# main.net
KiCad netlist of a schematic drawn in Altium Designer
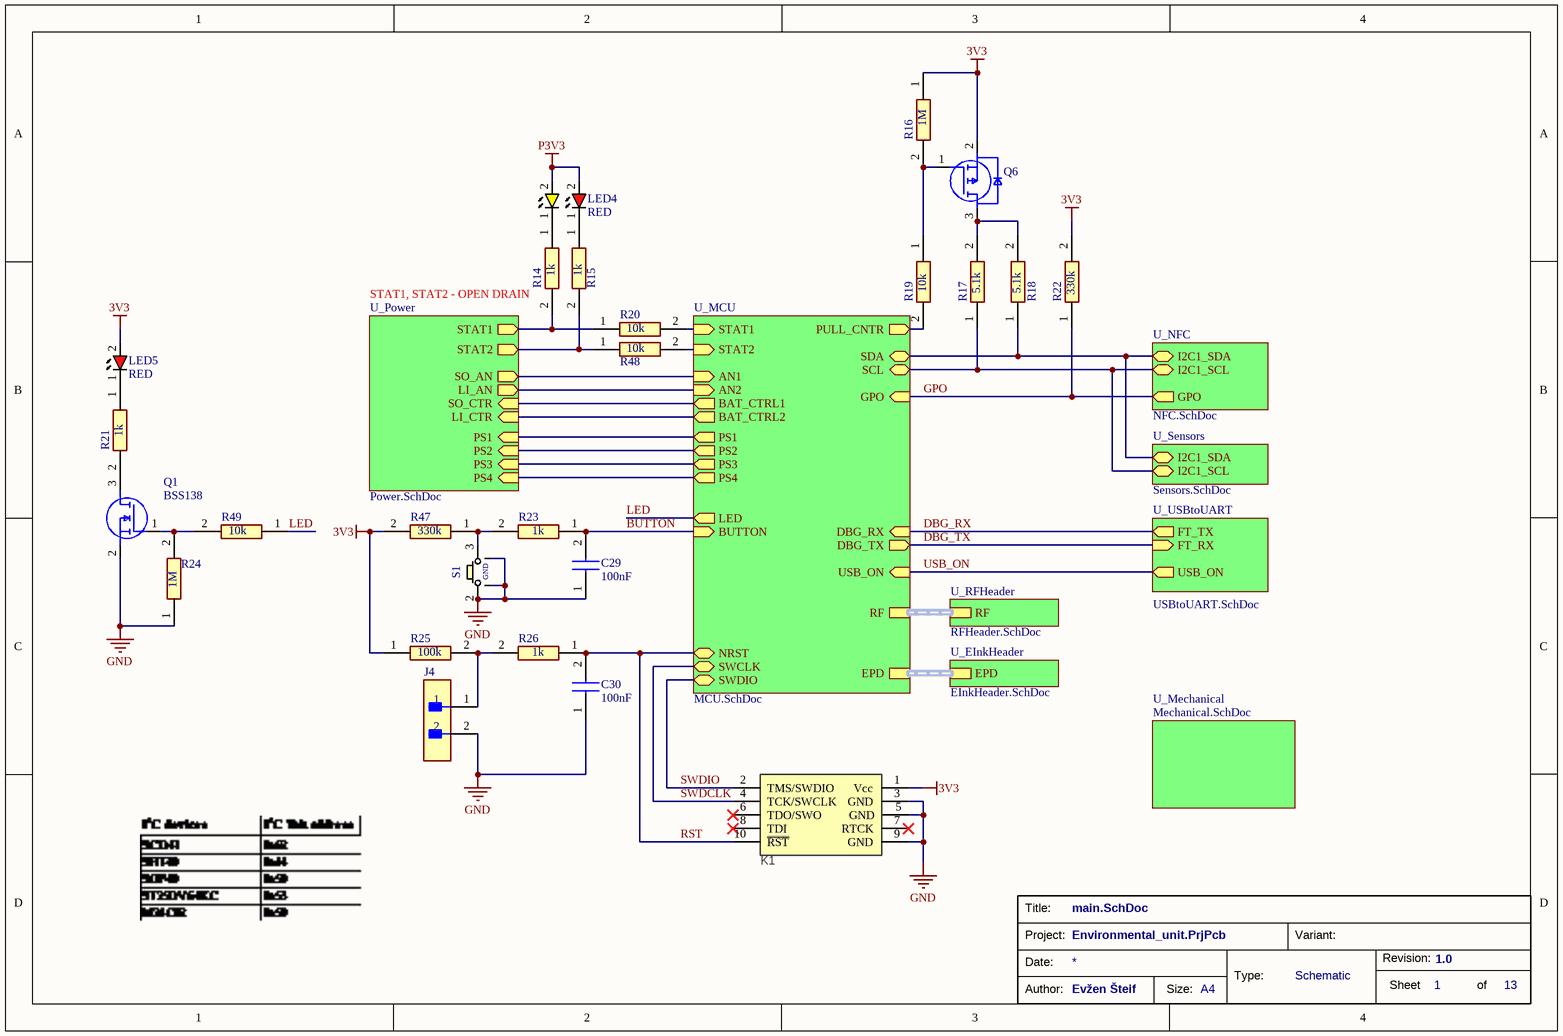
[diagram p0: main.SchDoc]

(export (version "E")
  (design (tool "Eeschema 10.0.6"))
  (components
    (comp (ref "C29")
      (value "100nF")
      (footprint "SamacSys:CAPC1005X70N")
      (description "Capacitor")
      (fields
        (field (name "MANUFACTURER_PART_NUMBER") "GRM155R61A104KA01D")
        (field (name "MOUSER PART NUMBER") "81-GRM155R61A104KA01")
      )
      (libsource (lib "*") (part "GRM155R61A104KA01D"))
    )
    (comp (ref "C30")
      (value "100nF")
      (footprint "SamacSys:CAPC1005X70N")
      (description "Capacitor")
      (fields
        (field (name "MANUFACTURER_PART_NUMBER") "GRM155R61A104KA01D")
        (field (name "MOUSER PART NUMBER") "81-GRM155R61A104KA01")
      )
      (libsource (lib "*") (part "GRM155R61A104KA01D"))
    )
    (comp (ref "J4")
      (value "M20-9990246")
      (footprint "FP-M20-9990246-MFG")
      (description "CONN HEADER VERT 2POS 2.54MM")
      (fields
        (field (name "OCTOPART") "https://octopart.com/m20-9990246-harwin-2590635")
        (field (name "MANUFACTURER") "Harwin")
      )
      (libsource (lib "Altium Content Vault") (part "3bc925449376181038e59eaffc5286c"))
    )
    (comp (ref "K1")
      (value "3220-10-0100-00")
      (footprint "IntLibGenerator:TH_CON_MHDR2X5_PIT50_KEY")
      (description "Cortex ARM JTAG 10 Pin, Header")
      (fields
        (field (name "PARTNUMBER") "TEST_00015")
        (field (name "MANUFACTURER") "CNC Tech")
        (field (name "AUTOR") "Krutina")
        (field (name "DESIGNER") "Krahulec")
        (field (name "LIBRARIAN") "Krahulec")
      )
      (libsource (lib "SamacSys") (part "TEST_00015"))
    )
    (comp (ref "LED3")
      (value "150060YS75000")
      (footprint "SamacSys:LEDC1608X80N")
      (description "LED")
      (fields (field (name "MOUSER PART NUMBER") "710-150060YS75000"))
      (libsource (lib "SamacSys") (part "150060YS75000"))
    )
    (comp (ref "LED4")
      (value "RED")
      (footprint "SamacSys:LEDC1608X80N")
      (description "LED")
      (fields
        (field (name "MANUFACTURER_PART_NUMBER") "150060RS75000")
        (field (name "MOUSER PART NUMBER") "710-150060RS75000")
      )
      (libsource (lib "SamacSys") (part "150060RS55040"))
    )
    (comp (ref "LED5")
      (value "RED")
      (footprint "SamacSys:LEDC1608X80N")
      (description "LED")
      (fields
        (field (name "MANUFACTURER_PART_NUMBER") "150060RS75000")
        (field (name "MOUSER PART NUMBER") "710-150060RS75000")
      )
      (libsource (lib "SamacSys") (part "150060RS55040"))
    )
    (comp (ref "Q1")
      (value "BSS138")
      (footprint "SamacSys:SOT95P240X120-3N")
      (description "MOSFET (N-Channel)")
      (fields (field (name "MOUSER PART NUMBER") "512-BSS138"))
      (libsource (lib "*") (part "BSS138"))
    )
    (comp (ref "Q6")
      (value "SSM3J358R,LF")
      (footprint "SamacSys:SOTFL95P240X88-3N")
      (description "MOSFET (P-Channel)")
      (fields (field (name "MOUSER PART NUMBER") "757-SSM3J358RLF"))
      (libsource (lib "SamacSys") (part "SSM3J358R,LF"))
    )
    (comp (ref "R14")
      (value "1k")
      (footprint "SamacSys:RESC1005X35N")
      (description "Resistor")
      (fields
        (field (name "MANUFACTURER_PART_NUMBER") "RT0402FRE071KL")
        (field (name "ARROW PART NUMBER") "RT0402FRE07100KL")
      )
      (libsource (lib "") (part "RT0402FRE071KL_1"))
    )
    (comp (ref "R15")
      (value "1k")
      (footprint "SamacSys:RESC1005X35N")
      (description "Resistor")
      (fields
        (field (name "MANUFACTURER_PART_NUMBER") "RT0402FRE071KL")
        (field (name "ARROW PART NUMBER") "RT0402FRE07100KL")
      )
      (libsource (lib "") (part "RT0402FRE071KL_1"))
    )
    (comp (ref "R16")
      (value "1M")
      (footprint "SamacSys:RESC1005X40N")
      (description "Resistor")
      (fields
        (field (name "MANUFACTURER_PART_NUMBER") "RC0402FR-071ML")
        (field (name "MOUSER PART NUMBER") "603-RC0402FR-071ML")
      )
      (libsource (lib "*") (part "RC0402FR-071ML"))
    )
    (comp (ref "R17")
      (value "5.1k")
      (footprint "SamacSys:RESC1005X35N")
      (description "Resistor")
      (fields (field (name "MANUFACTURER_PART_NUMBER") "RT0402FRE075K1L"))
      (libsource (lib "SamacSys") (part "RT0402FRE075K1L"))
    )
    (comp (ref "R18")
      (value "5.1k")
      (footprint "SamacSys:RESC1005X35N")
      (description "Resistor")
      (fields (field (name "MANUFACTURER_PART_NUMBER") "RT0402FRE075K1L"))
      (libsource (lib "SamacSys") (part "RT0402FRE075K1L"))
    )
    (comp (ref "R19")
      (value "10k")
      (footprint "SamacSys:RESC1005X35N")
      (description "Resistor")
      (fields
        (field (name "MANUFACTURER_PART_NUMBER") "RT0402FRE0710KL")
        (field (name "MOUSER PART NUMBER") "603-RT0402FRE0710KL")
      )
      (libsource (lib "") (part "RT0402FRE0710KL_2"))
    )
    (comp (ref "R20")
      (value "10k")
      (footprint "SamacSys:RESC1005X35N")
      (description "Resistor")
      (fields
        (field (name "MANUFACTURER_PART_NUMBER") "RT0402FRE0710KL")
        (field (name "MOUSER PART NUMBER") "603-RT0402FRE0710KL")
      )
      (libsource (lib "SamacSys") (part "RT0402FRE0710KL"))
    )
    (comp (ref "R21")
      (value "1k")
      (footprint "SamacSys:RESC1005X35N")
      (description "Resistor")
      (fields
        (field (name "MANUFACTURER_PART_NUMBER") "RT0402FRE071KL")
        (field (name "ARROW PART NUMBER") "RT0402FRE07100KL")
      )
      (libsource (lib "") (part "RT0402FRE071KL_1"))
    )
    (comp (ref "R22")
      (value "330k")
      (footprint "SamacSys:RESC1005X40N")
      (description "Resistor")
      (fields (field (name "MANUFACTURER_PART_NUMBER") "RC0402BR-07330KL"))
      (libsource (lib "") (part "RC0402BR-07330KL_1"))
    )
    (comp (ref "R23")
      (value "1k")
      (footprint "SamacSys:RESC1005X35N")
      (description "Resistor")
      (fields
        (field (name "MANUFACTURER_PART_NUMBER") "RT0402FRE071KL")
        (field (name "ARROW PART NUMBER") "RT0402FRE07100KL")
      )
      (libsource (lib "SamacSys") (part "RT0402FRE071KL"))
    )
    (comp (ref "R24")
      (value "1M")
      (footprint "SamacSys:RESC1005X40N")
      (description "Resistor")
      (fields
        (field (name "MANUFACTURER_PART_NUMBER") "RC0402FR-071ML")
        (field (name "MOUSER PART NUMBER") "603-RC0402FR-071ML")
      )
      (libsource (lib "") (part "RC0402FR-071ML_1"))
    )
    (comp (ref "R25")
      (value "100k")
      (footprint "SamacSys:RESC1005X35N")
      (description "Resistor")
      (fields
        (field (name "MANUFACTURER_PART_NUMBER") "RT0402FRE07100KL")
        (field (name "MOUSER PART NUMBER") "603-RT0402FRE07100KL")
      )
      (libsource (lib "*") (part "RT0402FRE07100KL"))
    )
    (comp (ref "R26")
      (value "1k")
      (footprint "SamacSys:RESC1005X35N")
      (description "Resistor")
      (fields
        (field (name "MANUFACTURER_PART_NUMBER") "RT0402FRE071KL")
        (field (name "ARROW PART NUMBER") "RT0402FRE07100KL")
      )
      (libsource (lib "SamacSys") (part "RT0402FRE071KL"))
    )
    (comp (ref "R47")
      (value "330k")
      (footprint "SamacSys:RESC1005X40N")
      (description "Resistor")
      (fields (field (name "MANUFACTURER_PART_NUMBER") "RC0402BR-07330KL"))
      (libsource (lib "SamacSys") (part "RC0402BR-07330KL"))
    )
    (comp (ref "R48")
      (value "10k")
      (footprint "SamacSys:RESC1005X35N")
      (description "Resistor")
      (fields
        (field (name "MANUFACTURER_PART_NUMBER") "RT0402FRE0710KL")
        (field (name "MOUSER PART NUMBER") "603-RT0402FRE0710KL")
      )
      (libsource (lib "SamacSys") (part "RT0402FRE0710KL"))
    )
    (comp (ref "R49")
      (value "10k")
      (footprint "SamacSys:RESC1005X35N")
      (description "Resistor")
      (fields
        (field (name "MANUFACTURER_PART_NUMBER") "RT0402FRE0710KL")
        (field (name "MOUSER PART NUMBER") "603-RT0402FRE0710KL")
      )
      (libsource (lib "") (part "RT0402FRE0710KL_1"))
    )
    (comp (ref "S1")
      (value "431256038716")
      (footprint "SamacSys:431256038716")
      (description "Switch")
      (fields (field (name "MOUSER PART NUMBER") "710-431256038716"))
      (libsource (lib "SamacSys") (part "431256038716"))
    )
  )
  (nets
    (net (code "3") (name "/BUTTON") (class "Default")
      (node (ref "C29") (pin "2") (pinfunction "2_2") (pintype "passive"))
      (node (ref "R23") (pin "1") (pinfunction "1_1") (pintype "passive"))
    )
    (net (code "7") (name "/GPO") (class "Default")
      (node (ref "R22") (pin "1") (pinfunction "1_1") (pintype "passive"))
    )
    (net (code "8") (name "/I2C1_SCL") (class "Default")
      (node (ref "R17") (pin "1") (pinfunction "1_1") (pintype "passive"))
    )
    (net (code "9") (name "/I2C1_SDA") (class "Default")
      (node (ref "R18") (pin "1") (pinfunction "1_1") (pintype "passive"))
    )
    (net (code "10") (name "/LED") (class "Default")
      (node (ref "R49") (pin "1") (pinfunction "1_1") (pintype "passive"))
    )
    (net (code "16") (name "/PULL_CNTR") (class "Default")
      (node (ref "R19") (pin "2") (pinfunction "2_2") (pintype "passive"))
    )
    (net (code "18") (name "/RST") (class "Default")
      (node (ref "C30") (pin "2") (pinfunction "2_2") (pintype "passive"))
      (node (ref "K1") (pin "10") (pinfunction "~{RST}_10") (pintype "passive"))
      (node (ref "R26") (pin "1") (pinfunction "1_1") (pintype "passive"))
    )
    (net (code "20") (name "/STAT1") (class "Default")
      (node (ref "R14") (pin "2") (pinfunction "2_2") (pintype "passive"))
      (node (ref "R20") (pin "1") (pinfunction "1_1") (pintype "passive"))
    )
    (net (code "21") (name "/STAT1_1") (class "Default")
      (node (ref "R20") (pin "2") (pinfunction "2_2") (pintype "passive"))
    )
    (net (code "22") (name "/STAT2") (class "Default")
      (node (ref "R15") (pin "2") (pinfunction "2_2") (pintype "passive"))
      (node (ref "R48") (pin "1") (pinfunction "1_1") (pintype "passive"))
    )
    (net (code "23") (name "/STAT2_1") (class "Default")
      (node (ref "R48") (pin "2") (pinfunction "2_2") (pintype "passive"))
    )
    (net (code "24") (name "/SWDCLK") (class "Default")
      (node (ref "K1") (pin "4") (pinfunction "TCK/SWCLK_4") (pintype "passive"))
    )
    (net (code "25") (name "/SWDIO") (class "Default")
      (node (ref "K1") (pin "2") (pinfunction "TMS/SWDIO_2") (pintype "passive"))
    )
    (net (code "27") (name "3V3") (class "Default")
      (node (ref "K1") (pin "1") (pinfunction "Vcc_1") (pintype "passive"))
      (node (ref "LED5") (pin "2") (pinfunction "A_2") (pintype "passive"))
      (node (ref "Q6") (pin "2") (pinfunction "S_2") (pintype "passive"))
      (node (ref "R16") (pin "1") (pinfunction "1_1") (pintype "passive"))
      (node (ref "R22") (pin "2") (pinfunction "2_2") (pintype "passive"))
      (node (ref "R25") (pin "1") (pinfunction "1_1") (pintype "passive"))
      (node (ref "R47") (pin "2") (pinfunction "2_2") (pintype "passive"))
    )
    (net (code "28") (name "GND") (class "Default")
      (node (ref "C29") (pin "1") (pinfunction "1_1") (pintype "passive"))
      (node (ref "C30") (pin "1") (pinfunction "1_1") (pintype "passive"))
      (node (ref "J4") (pin "2") (pinfunction "2_2") (pintype "passive"))
      (node (ref "K1") (pin "3") (pinfunction "GND_3") (pintype "passive"))
      (node (ref "K1") (pin "5") (pinfunction "GND_5") (pintype "passive"))
      (node (ref "K1") (pin "9") (pinfunction "GND_9") (pintype "passive"))
      (node (ref "Q1") (pin "2") (pinfunction "S_2") (pintype "passive"))
      (node (ref "R24") (pin "1") (pinfunction "1_1") (pintype "passive"))
      (node (ref "S1") (pin "1") (pinfunction "1_1") (pintype "passive"))
      (node (ref "S1") (pin "2") (pinfunction "2_2") (pintype "passive"))
      (node (ref "S1") (pin "4") (pinfunction "4_4") (pintype "passive"))
    )
    (net (code "29") (name "Net-(J4-Pad1)") (class "Default")
      (node (ref "J4") (pin "1") (pinfunction "1_1") (pintype "passive"))
      (node (ref "R25") (pin "2") (pinfunction "2_2") (pintype "passive"))
      (node (ref "R26") (pin "2") (pinfunction "2_2") (pintype "passive"))
    )
    (net (code "30") (name "Net-(LED3-K)") (class "Default")
      (node (ref "LED3") (pin "1") (pinfunction "K_1") (pintype "passive"))
      (node (ref "R14") (pin "1") (pinfunction "1_1") (pintype "passive"))
    )
    (net (code "31") (name "Net-(LED4-K)") (class "Default")
      (node (ref "LED4") (pin "1") (pinfunction "K_1") (pintype "passive"))
      (node (ref "R15") (pin "1") (pinfunction "1_1") (pintype "passive"))
    )
    (net (code "32") (name "Net-(LED5-K)") (class "Default")
      (node (ref "LED5") (pin "1") (pinfunction "K_1") (pintype "passive"))
      (node (ref "R21") (pin "1") (pinfunction "1_1") (pintype "passive"))
    )
    (net (code "33") (name "Net-(Q1-D)") (class "Default")
      (node (ref "Q1") (pin "3") (pinfunction "D_3") (pintype "passive"))
      (node (ref "R21") (pin "2") (pinfunction "2_2") (pintype "passive"))
    )
    (net (code "34") (name "Net-(Q1-G)") (class "Default")
      (node (ref "Q1") (pin "1") (pinfunction "G_1") (pintype "passive"))
      (node (ref "R24") (pin "2") (pinfunction "2_2") (pintype "passive"))
      (node (ref "R49") (pin "2") (pinfunction "2_2") (pintype "passive"))
    )
    (net (code "35") (name "Net-(Q6-D)") (class "Default")
      (node (ref "Q6") (pin "3") (pinfunction "D_3") (pintype "passive"))
      (node (ref "R17") (pin "2") (pinfunction "2_2") (pintype "passive"))
      (node (ref "R18") (pin "2") (pinfunction "2_2") (pintype "passive"))
    )
    (net (code "36") (name "Net-(Q6-G)") (class "Default")
      (node (ref "Q6") (pin "1") (pinfunction "G_1") (pintype "passive"))
      (node (ref "R16") (pin "2") (pinfunction "2_2") (pintype "passive"))
      (node (ref "R19") (pin "1") (pinfunction "1_1") (pintype "passive"))
    )
    (net (code "37") (name "Net-(R23-Pad2)") (class "Default")
      (node (ref "R23") (pin "2") (pinfunction "2_2") (pintype "passive"))
      (node (ref "R47") (pin "1") (pinfunction "1_1") (pintype "passive"))
      (node (ref "S1") (pin "3") (pinfunction "3_3") (pintype "passive"))
    )
    (net (code "38") (name "P3V3") (class "Default")
      (node (ref "LED3") (pin "2") (pinfunction "A_2") (pintype "passive"))
      (node (ref "LED4") (pin "2") (pinfunction "A_2") (pintype "passive"))
    )
    (net (code "39") (name "unconnected-(K1-RTCK-Pad7)") (class "Default")
      (node (ref "K1") (pin "7") (pinfunction "RTCK_7") (pintype "passive+no_connect"))
    )
    (net (code "40") (name "unconnected-(K1-TDI-Pad8)") (class "Default")
      (node (ref "K1") (pin "8") (pinfunction "TDI_8") (pintype "passive+no_connect"))
    )
    (net (code "41") (name "unconnected-(K1-TDO{slash}SWO-Pad6)") (class "Default")
      (node (ref "K1") (pin "6") (pinfunction "TDO/SWO_6") (pintype "passive+no_connect"))
    )
  )
)
